# CLOCKS.net
KiCad netlist of a schematic drawn in Altium Designer
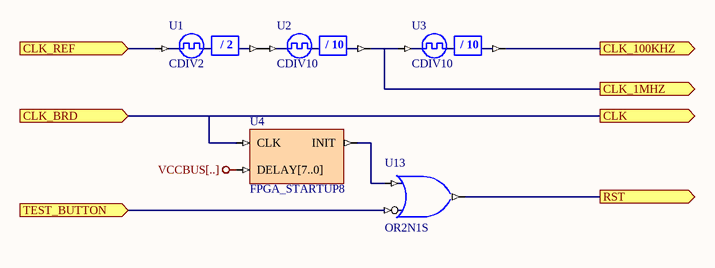
[diagram p0: CLOCKS.SCHDOC]

(export (version "E")
  (design (tool "Eeschema 10.0.6"))
  (components
    (comp (ref "U1")
      (value "CDIV2")
      (description "Clock Divider by 2")
      (fields (field (name "PUBLISHER") "Altium Limited"))
      (libsource (lib "FPGA Generic") (part "CDIV2"))
    )
    (comp (ref "U2")
      (value "CDIV10")
      (description "Clock Divider by 10")
      (fields (field (name "PUBLISHER") "Altium Limited"))
      (libsource (lib "FPGA Generic") (part "CDIV10"))
    )
    (comp (ref "U3")
      (value "CDIV10")
      (description "Clock Divider by 10")
      (fields (field (name "PUBLISHER") "Altium Limited"))
      (libsource (lib "FPGA Generic") (part "CDIV10"))
    )
    (comp (ref "U4")
      (value "FPGA_STARTUP8")
      (description "FPGA Startup With 8 Bit Delay")
      (fields (field (name "PUBLISHER") "Altium Hobart Technology Centre"))
      (libsource (lib "FPGA Peripherals") (part "FPGA_STARTUP8"))
    )
    (comp (ref "U13")
      (value "OR2N1S")
      (description "2-Input OR Gate with Active Low A Input, Single Pin Version")
      (fields (field (name "PUBLISHER") "Altium Limited"))
      (libsource (lib "FPGA Generic") (part "OR2N1S"))
    )
  )
  (nets
    (net (code "3") (name "/CLK_1MHZ") (class "Default")
      (node (ref "U2") (pin "CLKDV") (pinfunction "CLKDV_CLKDV") (pintype "output"))
      (node (ref "U3") (pin "CLKIN") (pinfunction "CLKIN_CLKIN") (pintype "input"))
    )
    (net (code "4") (name "/CLK_100KHZ") (class "Default")
      (node (ref "U3") (pin "CLKDV") (pinfunction "CLKDV_CLKDV") (pintype "output"))
    )
    (net (code "5") (name "/CLK_REF") (class "Default")
      (node (ref "U1") (pin "CLKIN") (pinfunction "CLKIN_CLKIN") (pintype "input"))
    )
    (net (code "6") (name "/RST") (class "Default")
      (node (ref "U13") (pin "O") (pinfunction "O_O") (pintype "output"))
    )
    (net (code "7") (name "/TEST_BUTTON") (class "Default")
      (node (ref "U13") (pin "I0") (pinfunction "I0_I0") (pintype "input"))
    )
    (net (code "8") (name "Net-(U1-PadCLKDV)") (class "Default")
      (node (ref "U1") (pin "CLKDV") (pinfunction "CLKDV_CLKDV") (pintype "output"))
      (node (ref "U2") (pin "CLKIN") (pinfunction "CLKIN_CLKIN") (pintype "input"))
    )
    (net (code "9") (name "Net-(U13-PadI1)") (class "Default")
      (node (ref "U13") (pin "I1") (pinfunction "I1_I1") (pintype "input"))
      (node (ref "U4") (pin "INIT") (pinfunction "INIT_INIT") (pintype "output"))
    )
    (net (code "10") (name "VCCBUS[..]") (class "Default")
      (node (ref "U4") (pin "DELAY[7..0]") (pinfunction "DELAY[7..0]_DELAY[7..0]") (pintype "input"))
    )
    (net (code "11") (name "unconnected-(U4-PadCLK)") (class "Default")
      (node (ref "U4") (pin "CLK") (pinfunction "CLK_CLK") (pintype "input"))
    )
  )
)
